# Microcontroller.net
KiCad netlist of a schematic drawn in Altium Designer
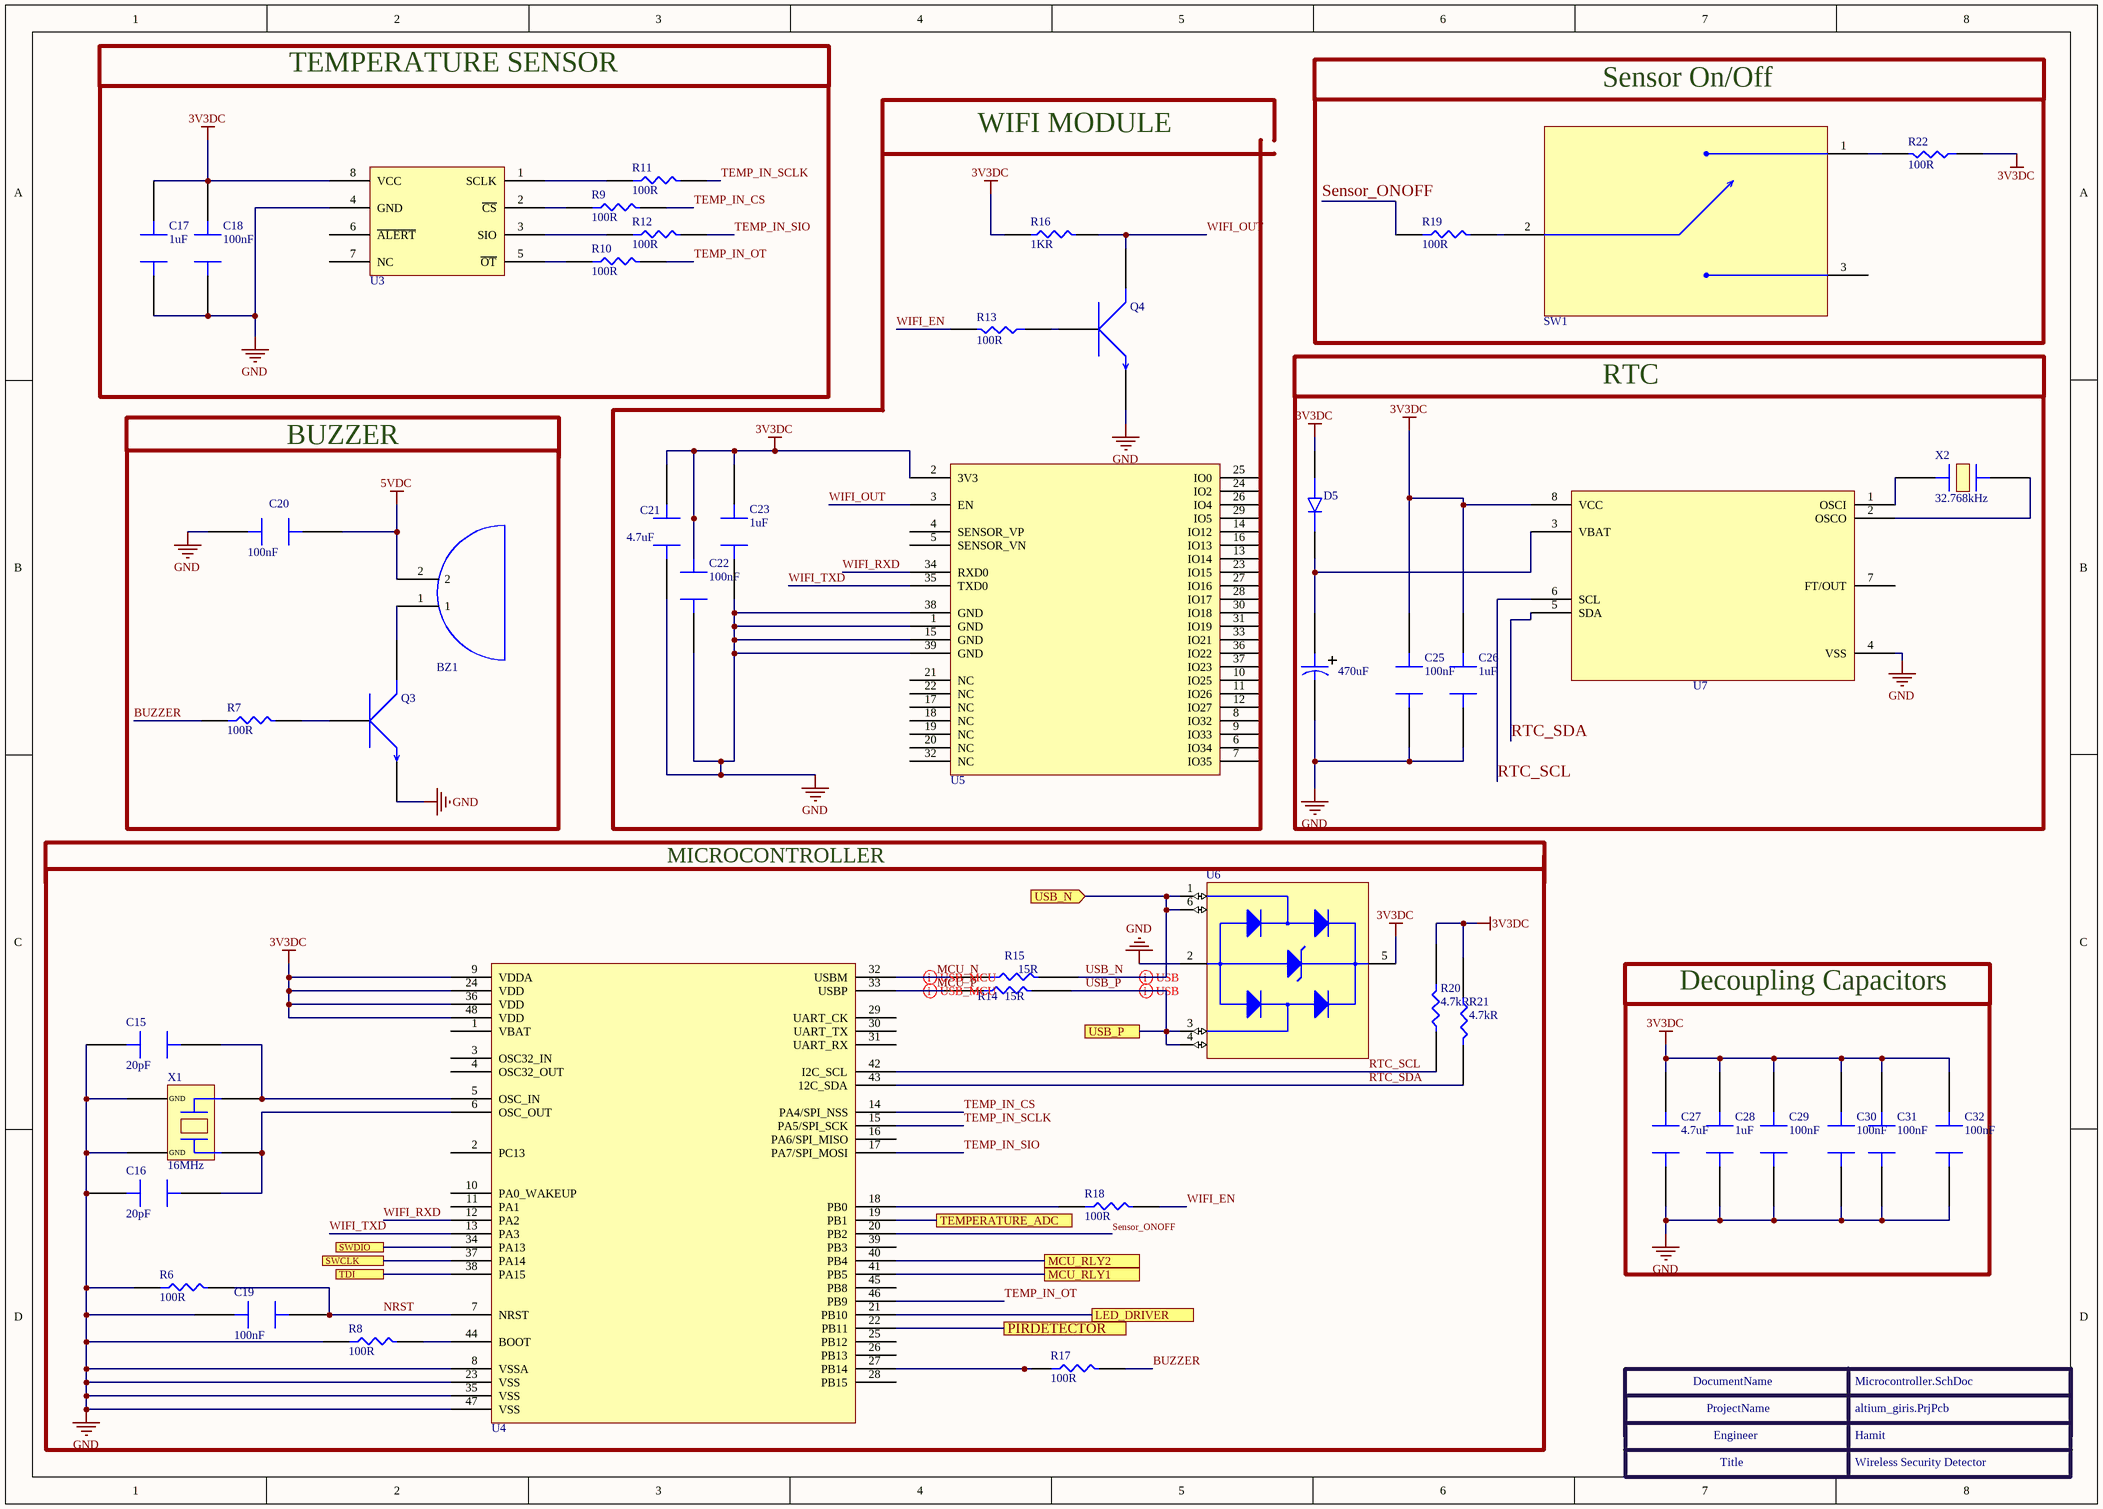
[diagram p0: Microcontroller.SchDoc]

(export (version "E")
  (design (tool "Eeschema 10.0.6"))
  (components
    (comp (ref "BZ1")
      (value "CMI-9605IC-0580T")
      (footprint "CMI-9605IC-0580T")
      (description "Buzzers Indicator, Internally Driven Magnetic 30mA 2.7kHz 80dB @ 5V, 10cm Through Hole PC Pins")
      (fields (field (name "MANUFACTURER") "CUI Devices") (field (name "DESIGNED BY") "Hamit"))
      (libsource (lib "giris_intlib") (part "CMI-9605IC-0580T"))
    )
    (comp (ref "C15")
      (value "CL10C200JB8NNNC")
      (footprint "CAP_0603")
      (fields
        (field (name "MANUFACTURER") "Samsung")
        (field (name "TOLERANCE") "5%")
        (field (name "VOLTAGE") "50V")
        (field (name "CAPACITANCE") "20pF")
        (field (name "DESIGNED BY") "Hamit")
      )
      (libsource (lib "giris_intlib") (part "CAP CER 20PF"))
    )
    (comp (ref "C16")
      (value "CL10C200JB8NNNC")
      (footprint "CAP_0603")
      (fields
        (field (name "MANUFACTURER") "Samsung")
        (field (name "TOLERANCE") "5%")
        (field (name "VOLTAGE") "50V")
        (field (name "CAPACITANCE") "20pF")
        (field (name "DESIGNED BY") "Hamit")
      )
      (libsource (lib "giris_intlib") (part "CAP CER 20PF"))
    )
    (comp (ref "C17")
      (value "CAP CER 1uF 0805")
      (footprint "cap_0805")
      (description "0805 0.1 uF ±10 % Tolerance 50 V X7R Multilayer Ceramic Capacitors")
      (fields
        (field (name "MANUFACTURER") "Samsung")
        (field (name "MANUFACTURER PART NUMBER") "CL21B104KBFNNNE")
        (field (name "CAPACITANCE") "1uF")
        (field (name "DESIGNED BY") "Hamit")
      )
      (libsource (lib "giris_intlib") (part "CAP CER 1uF 0805"))
    )
    (comp (ref "C18")
      (value "CL21B104KBCNNNC")
      (footprint "cap_0805")
      (fields
        (field (name "MANUFACTURER") "Samsung")
        (field (name "TOLERANCE") "10%")
        (field (name "VOLTAGE") "50V")
        (field (name "CAPACITANCE") "100nF")
        (field (name "DESIGNED BY") "Hamit")
      )
      (libsource (lib "giris_intlib") (part "CAP cer 100nF 0805"))
    )
    (comp (ref "C19")
      (value "CAP CER 100nF 0603")
      (footprint "CAP_0603")
      (fields
        (field (name "MANUFACTURER") "KEMET")
        (field (name "MANUFACTURER PART NUMBER") "C0603C104K5RACTU")
        (field (name "TOLERANCE") "10%")
        (field (name "CAPACITANCE") "100nF")
        (field (name "DESIGNED BY") "Hamit")
      )
      (libsource (lib "giris_intlib") (part "CAP CER 100nF 0603"))
    )
    (comp (ref "C20")
      (value "CAP CER 100nF 0603")
      (footprint "CAP_0603")
      (fields
        (field (name "MANUFACTURER") "KEMET")
        (field (name "MANUFACTURER PART NUMBER") "C0603C104K5RACTU")
        (field (name "TOLERANCE") "10%")
        (field (name "CAPACITANCE") "100nF")
        (field (name "DESIGNED BY") "Hamit")
      )
      (libsource (lib "giris_intlib") (part "CAP CER 100nF 0603"))
    )
    (comp (ref "C21")
      (value "CL21A475KAQNNNE")
      (footprint "cap_0805")
      (fields
        (field (name "MANUFACTURER") "Samsung")
        (field (name "TOLERANCE") "10%")
        (field (name "CAPACITANCE") "4.7uF")
        (field (name "DESIGNED BY") "Hamit")
      )
      (libsource (lib "giris_intlib") (part "cap_0805_4.7uF"))
    )
    (comp (ref "C22")
      (value "CL21B104KBCNNNC")
      (footprint "cap_0805")
      (fields
        (field (name "MANUFACTURER") "Samsung")
        (field (name "TOLERANCE") "10%")
        (field (name "VOLTAGE") "50V")
        (field (name "CAPACITANCE") "100nF")
        (field (name "DESIGNED BY") "Hamit")
      )
      (libsource (lib "giris_intlib") (part "CAP cer 100nF 0805"))
    )
    (comp (ref "C23")
      (value "CAP CER 1uF 0805")
      (footprint "cap_0805")
      (description "0805 0.1 uF ±10 % Tolerance 50 V X7R Multilayer Ceramic Capacitors")
      (fields
        (field (name "MANUFACTURER") "Samsung")
        (field (name "MANUFACTURER PART NUMBER") "CL21B104KBFNNNE")
        (field (name "CAPACITANCE") "1uF")
        (field (name "DESIGNED BY") "Hamit")
      )
      (libsource (lib "giris_intlib") (part "CAP CER 1uF 0805"))
    )
    (comp (ref "C24")
      (value "ESH477M050AH4AA")
      (footprint "cap_ESH477M050AH4AA")
      (description "Cap, 470UF, 50V, Alu Elec, Radial")
      (fields
        (field (name "MANUFACTURER") "KEMET")
        (field (name "TOLERANCE") "20%")
        (field (name "CAPACITANCE") "470uF")
        (field (name "DESIGNED BY") "Hamit")
      )
      (libsource (lib "giris_intlib") (part "CAP ALU 470uF"))
    )
    (comp (ref "C25")
      (value "CAP CER 100nF 0603")
      (footprint "CAP_0603")
      (fields
        (field (name "MANUFACTURER") "KEMET")
        (field (name "MANUFACTURER PART NUMBER") "C0603C104K5RACTU")
        (field (name "TOLERANCE") "10%")
        (field (name "CAPACITANCE") "100nF")
        (field (name "DESIGNED BY") "Hamit")
      )
      (libsource (lib "giris_intlib") (part "CAP CER 100nF 0603"))
    )
    (comp (ref "C26")
      (value "CAP CER 1uF 0805")
      (footprint "cap_0805")
      (description "0805 0.1 uF ±10 % Tolerance 50 V X7R Multilayer Ceramic Capacitors")
      (fields
        (field (name "MANUFACTURER") "Samsung")
        (field (name "MANUFACTURER PART NUMBER") "CL21B104KBFNNNE")
        (field (name "CAPACITANCE") "1uF")
        (field (name "DESIGNED BY") "Hamit")
      )
      (libsource (lib "giris_intlib") (part "CAP CER 1uF 0805"))
    )
    (comp (ref "C27")
      (value "CL21A475KAQNNNE")
      (footprint "cap_0805")
      (fields
        (field (name "MANUFACTURER") "Samsung")
        (field (name "TOLERANCE") "10%")
        (field (name "CAPACITANCE") "4.7uF")
        (field (name "DESIGNED BY") "Hamit")
      )
      (libsource (lib "giris_intlib") (part "CAP CER 4.7 uF"))
    )
    (comp (ref "C28")
      (value "CAP CER 1uF 0805")
      (footprint "cap_0805")
      (description "0805 0.1 uF ±10 % Tolerance 50 V X7R Multilayer Ceramic Capacitors")
      (fields
        (field (name "MANUFACTURER") "Samsung")
        (field (name "MANUFACTURER PART NUMBER") "CL21B104KBFNNNE")
        (field (name "CAPACITANCE") "1uF")
        (field (name "DESIGNED BY") "Hamit")
      )
      (libsource (lib "giris_intlib") (part "CAP CER 1uF 0805"))
    )
    (comp (ref "C29")
      (value "CAP CER 100nF 0603")
      (footprint "CAP_0603")
      (fields
        (field (name "MANUFACTURER") "KEMET")
        (field (name "MANUFACTURER PART NUMBER") "C0603C104K5RACTU")
        (field (name "TOLERANCE") "10%")
        (field (name "CAPACITANCE") "100nF")
        (field (name "DESIGNED BY") "Hamit")
      )
      (libsource (lib "giris_intlib") (part "CAP CER 100nF 0603"))
    )
    (comp (ref "C30")
      (value "CAP CER 100nF 0603")
      (footprint "CAP_0603")
      (fields
        (field (name "MANUFACTURER") "KEMET")
        (field (name "MANUFACTURER PART NUMBER") "C0603C104K5RACTU")
        (field (name "TOLERANCE") "10%")
        (field (name "CAPACITANCE") "100nF")
        (field (name "DESIGNED BY") "Hamit")
      )
      (libsource (lib "giris_intlib") (part "CAP CER 100nF 0603"))
    )
    (comp (ref "C31")
      (value "CAP CER 100nF 0603")
      (footprint "CAP_0603")
      (fields
        (field (name "MANUFACTURER") "KEMET")
        (field (name "MANUFACTURER PART NUMBER") "C0603C104K5RACTU")
        (field (name "TOLERANCE") "10%")
        (field (name "CAPACITANCE") "100nF")
        (field (name "DESIGNED BY") "Hamit")
      )
      (libsource (lib "giris_intlib") (part "CAP CER 100nF 0603"))
    )
    (comp (ref "C32")
      (value "CAP CER 100nF 0603")
      (footprint "CAP_0603")
      (fields
        (field (name "MANUFACTURER") "KEMET")
        (field (name "MANUFACTURER PART NUMBER") "C0603C104K5RACTU")
        (field (name "TOLERANCE") "10%")
        (field (name "CAPACITANCE") "100nF")
        (field (name "DESIGNED BY") "Hamit")
      )
      (libsource (lib "giris_intlib") (part "CAP CER 100nF 0603"))
    )
    (comp (ref "D5")
      (value "DIODE GEN PURP 75V 150MA SOD323F")
      (footprint "1N4148WS")
      (description "ON SEMICONDUCTOR - 1N4148WS - Small Signal Diode, Single, 75 V, 150 mA, 1 V, 4 ns")
      (fields
        (field (name "MANUFACTURER") "ON Semiconductor / Fairchild")
        (field (name "MANUFACTURER PART NUMBER") "1N4148WS")
        (field (name "DESIGNED BY") "Hamit")
      )
      (libsource (lib "giris_intlib") (part "1N4148WS"))
    )
    (comp (ref "Q3")
      (value "MMBT3904-7-F")
      (footprint "SSM3K357R,LF")
      (description "Transistor General Purpose BJT NPN 40 Volt 0.2A Automotive 3-Pin SOT-23")
      (fields (field (name "MANUFACTURER") "Diodes Zetex") (field (name "DESIGNED BY") "Hamit"))
      (libsource (lib "giris_intlib") (part "MMBT3904-7-F"))
    )
    (comp (ref "Q4")
      (value "MMBT3904-7-F")
      (footprint "SSM3K357R,LF")
      (description "Transistor General Purpose BJT NPN 40 Volt 0.2A Automotive 3-Pin SOT-23")
      (fields (field (name "MANUFACTURER") "Diodes Zetex") (field (name "DESIGNED BY") "Hamit"))
      (libsource (lib "giris_intlib") (part "MMBT3904-7-F"))
    )
    (comp (ref "R6")
      (value "RC0603FR-7W100RL")
      (footprint "RES_0603")
      (description "RESISTOR, 0603, 100R, 1%")
      (fields
        (field (name "MANUFACTURER") "Yageo")
        (field (name "TOLERANCE") "1%")
        (field (name "RESISTANCE") "100R")
      )
      (libsource (lib "giris_intlib") (part "RES 100 OHm"))
    )
    (comp (ref "R7")
      (value "RC0603FR-7W100RL")
      (footprint "RES_0603")
      (description "RESISTOR, 0603, 100R, 1%")
      (fields
        (field (name "MANUFACTURER") "Yageo")
        (field (name "TOLERANCE") "1%")
        (field (name "RESISTANCE") "100R")
      )
      (libsource (lib "giris_intlib") (part "RES 100 OHM"))
    )
    (comp (ref "R8")
      (value "RC0603FR-7W100RL")
      (footprint "RES_0603")
      (description "RESISTOR, 0603, 100R, 1%")
      (fields
        (field (name "MANUFACTURER") "Yageo")
        (field (name "TOLERANCE") "1%")
        (field (name "RESISTANCE") "100R")
      )
      (libsource (lib "giris_intlib") (part "RES 100 OHm"))
    )
    (comp (ref "R9")
      (value "RC0603FR-7W100RL")
      (footprint "RES_0603")
      (description "RESISTOR, 0603, 100R, 1%")
      (fields
        (field (name "MANUFACTURER") "Yageo")
        (field (name "TOLERANCE") "1%")
        (field (name "RESISTANCE") "100R")
      )
      (libsource (lib "giris_intlib") (part "RES 100 OHM"))
    )
    (comp (ref "R10")
      (value "RC0603FR-7W100RL")
      (footprint "RES_0603")
      (description "RESISTOR, 0603, 100R, 1%")
      (fields
        (field (name "MANUFACTURER") "Yageo")
        (field (name "TOLERANCE") "1%")
        (field (name "RESISTANCE") "100R")
      )
      (libsource (lib "giris_intlib") (part "RES 100 OHM"))
    )
    (comp (ref "R11")
      (value "RC0603FR-7W100RL")
      (footprint "RES_0603")
      (description "RESISTOR, 0603, 100R, 1%")
      (fields
        (field (name "MANUFACTURER") "Yageo")
        (field (name "TOLERANCE") "1%")
        (field (name "RESISTANCE") "100R")
      )
      (libsource (lib "giris_intlib") (part "RES 100 OHM"))
    )
    (comp (ref "R12")
      (value "RC0603FR-7W100RL")
      (footprint "RES_0603")
      (description "RESISTOR, 0603, 100R, 1%")
      (fields
        (field (name "MANUFACTURER") "Yageo")
        (field (name "TOLERANCE") "1%")
        (field (name "RESISTANCE") "100R")
      )
      (libsource (lib "giris_intlib") (part "RES 100 OHM"))
    )
    (comp (ref "R13")
      (value "RC0603FR-7W100RL")
      (footprint "RES_0603")
      (description "RESISTOR, 0603, 100R, 1%")
      (fields
        (field (name "MANUFACTURER") "Yageo")
        (field (name "TOLERANCE") "1%")
        (field (name "RESISTANCE") "100R")
      )
      (libsource (lib "giris_intlib") (part "RES 100 OHm"))
    )
    (comp (ref "R14")
      (value "rc0603jr-0715rl")
      (footprint "RES_0603")
      (fields
        (field (name "MANUFACTURER") "Yageo")
        (field (name "MANUFACTURER PART NUMBER") "RC0603JR-0715RL")
        (field (name "TOLERANCE") "5%")
        (field (name "RESISTANCE") "15R")
        (field (name "DESIGNED BY") "Hamit")
      )
      (libsource (lib "giris_intlib") (part "RES 15 OHM 0603"))
    )
    (comp (ref "R15")
      (value "rc0603jr-0715rl")
      (footprint "RES_0603")
      (fields
        (field (name "MANUFACTURER") "Yageo")
        (field (name "MANUFACTURER PART NUMBER") "RC0603JR-0715RL")
        (field (name "TOLERANCE") "5%")
        (field (name "RESISTANCE") "15R")
        (field (name "DESIGNED BY") "Hamit")
      )
      (libsource (lib "giris_intlib") (part "RES 15 OHM 0603"))
    )
    (comp (ref "R16")
      (value "RC0603FR-0710KL")
      (footprint "RES_0603")
      (description "RES 1K %1 OHM 0603 SMD")
      (fields
        (field (name "MANUFACTURER") "Yageo")
        (field (name "MANUFACTURER PART NUMBER") "RC0603JR-071KL")
        (field (name "RESISTANCE") "1KR")
        (field (name "DESIGNED BY") "Hamit")
      )
      (libsource (lib "giris_intlib") (part "RES 1K OHM 0603"))
    )
    (comp (ref "R17")
      (value "RC0603FR-7W100RL")
      (footprint "RES_0603")
      (description "RESISTOR, 0603, 100R, 1%")
      (fields
        (field (name "MANUFACTURER") "Yageo")
        (field (name "TOLERANCE") "1%")
        (field (name "RESISTANCE") "100R")
      )
      (libsource (lib "giris_intlib") (part "RES 100 OHM"))
    )
    (comp (ref "R18")
      (value "RC0603FR-7W100RL")
      (footprint "RES_0603")
      (description "RESISTOR, 0603, 100R, 1%")
      (fields
        (field (name "MANUFACTURER") "Yageo")
        (field (name "TOLERANCE") "1%")
        (field (name "RESISTANCE") "100R")
      )
      (libsource (lib "giris_intlib") (part "RES 100 OHM"))
    )
    (comp (ref "R19")
      (value "RC0603FR-7W100RL")
      (footprint "RES_0603")
      (description "RESISTOR, 0603, 100R, 1%")
      (fields
        (field (name "MANUFACTURER") "Yageo")
        (field (name "TOLERANCE") "1%")
        (field (name "RESISTANCE") "100R")
      )
      (libsource (lib "giris_intlib") (part "RES 100 OHM"))
    )
    (comp (ref "R20")
      (value "RC0603JR-074K7L")
      (footprint "RES_0603")
      (description "Res Thick Film 0603 4.7K Ohm 5% 0.1W(1/10W) ±100ppm/C Molded SMD Paper T/R")
      (fields
        (field (name "MANUFACTURER") "Yageo")
        (field (name "TOLERANCE") "5%")
        (field (name "RESISTANCE") "4.7kR")
        (field (name "DESIGNED BY") "Hamit")
      )
      (libsource (lib "giris_intlib") (part "RES 4K7 OHM"))
    )
    (comp (ref "R21")
      (value "RC0603JR-074K7L")
      (footprint "RES_0603")
      (description "Res Thick Film 0603 4.7K Ohm 5% 0.1W(1/10W) ±100ppm/C Molded SMD Paper T/R")
      (fields
        (field (name "MANUFACTURER") "Yageo")
        (field (name "TOLERANCE") "5%")
        (field (name "RESISTANCE") "4.7kR")
        (field (name "DESIGNED BY") "Hamit")
      )
      (libsource (lib "giris_intlib") (part "RES 4K7 OHM"))
    )
    (comp (ref "R22")
      (value "RC0603FR-7W100RL")
      (footprint "RES_0603")
      (description "RESISTOR, 0603, 100R, 1%")
      (fields
        (field (name "MANUFACTURER") "Yageo")
        (field (name "TOLERANCE") "1%")
        (field (name "RESISTANCE") "100R")
      )
      (libsource (lib "giris_intlib") (part "RES 100 OHM"))
    )
    (comp (ref "SW1")
      (value "EG1215AA")
      (footprint "EG1215AA")
      (description "Slide Switch, SPDT, 0.025A, 24V, SMD")
      (fields
        (field (name "MANUFACTURER") "E-Switch")
        (field (name "TOLERANCE") "4.95%")
        (field (name "DESIGNED BY") "Hamit")
      )
      (libsource (lib "giris_intlib") (part "EG1215AA"))
    )
    (comp (ref "U3")
      (value "MAX6662MSA+-ND")
      (footprint "LM2675MX-12/NOPB")
      (description "Temp Sensor Digital Serial (3-Wire, SPI) 8-Pin SOIC N Tube")
      (fields
        (field (name "MANUFACTURER") "Maxim")
        (field (name "MANUFACTURER PART NUMBER") "MAX6662MSA+")
        (field (name "DESIGNED BY") "Hamit")
      )
      (libsource (lib "giris_intlib") (part "MAX6662MSA+-ND"))
    )
    (comp (ref "U4")
      (value "STM32F103C6T7A")
      (footprint "LQFP-48")
      (description "IC MCU 32BIT 32KB FLASH 48LQFP")
      (fields (field (name "MANUFACTURER") "STMicroelectronics") (field (name "DESIGNED BY") "Hamit"))
      (libsource (lib "giris_intlib") (part "STM32F103C6T7A"))
    )
    (comp (ref "U5")
      (value "ESP32-WROOM-32E(4MB)")
      (footprint "ESP32-32")
      (fields (field (name "MANUFACTURER") "Espressif Systems") (field (name "DESIGNED BY") "Hamit"))
      (libsource (lib "giris_intlib") (part "ESP32-WROOM-32E(4MB)"))
    )
    (comp (ref "U6")
      (value "USBLC6-2SC6")
      (footprint "SOT23-6")
      (description "TVS DIODE 5.25V 17V SOT23-6")
      (fields (field (name "MANUFACTURER") "STMicroelectronics") (field (name "DESIGNED BY") "Hamit"))
      (libsource (lib "giris_intlib") (part "USB PROTECTION"))
    )
    (comp (ref "U7")
      (value "M41T00M6F")
      (footprint "LM2675MX-12/NOPB")
      (description "IC RTC CLK/CALENDAR I2C 8-SOIC")
      (fields (field (name "MANUFACTURER") "STMicroelectronics") (field (name "DESIGNED BY") "Hamit"))
      (libsource (lib "giris_intlib") (part "M41T00M6F"))
    )
    (comp (ref "X1")
      (value "ECS-160-20-30B-TR")
      (footprint "CRYSTAL_ECS-160-20-30B-TR")
      (description "CRYSTAL 16.0000MHZ 20PF SMD")
      (fields
        (field (name "MANUFACTURER") "ECS International")
        (field (name "TOLERANCE") "50ppm")
        (field (name "FREQUENCY") "16MHz")
        (field (name "DESIGNED BY") "Hamit")
      )
      (libsource (lib "giris_intlib") (part "CRYSTAL 16MHZ 20PF SMD"))
    )
    (comp (ref "X2")
      (value "ABS05-32.768KHZ-T")
      (footprint "ABS05_crystal")
      (description "ABRACON - ABS05-32.768KHZ-T - Crystal, 32.768 kHz, SMD, 1.6mm x 1mm, 12.5 pF, 20 ppm, ABS05 Series")
      (fields
        (field (name "MANUFACTURER") "Abracon")
        (field (name "TOLERANCE") "20ppm")
        (field (name "FREQUENCY") "32.768kHz")
        (field (name "DESIGNED BY") "Hamit")
      )
      (libsource (lib "giris_intlib") (part "CRYSTAL 32768kHz"))
    )
  )
  (nets
    (net (code "1") (name "/BUZZER") (class "Default")
      (node (ref "R17") (pin "2") (pinfunction "2_2") (pintype "passive"))
      (node (ref "R7") (pin "1") (pinfunction "1_1") (pintype "passive"))
    )
    (net (code "2") (name "/LED_DRIVER") (class "Default")
      (node (ref "U4") (pin "21") (pinfunction "PB10_21") (pintype "passive"))
    )
    (net (code "3") (name "/MCU_N") (class "Default")
      (node (ref "R15") (pin "1") (pinfunction "1_1") (pintype "passive"))
      (node (ref "U4") (pin "32") (pinfunction "USBM_32") (pintype "passive"))
    )
    (net (code "4") (name "/MCU_P") (class "Default")
      (node (ref "R14") (pin "1") (pinfunction "1_1") (pintype "passive"))
      (node (ref "U4") (pin "33") (pinfunction "USBP_33") (pintype "passive"))
    )
    (net (code "5") (name "/MCU_RLY1") (class "Default")
      (node (ref "U4") (pin "41") (pinfunction "PB5_41") (pintype "passive"))
    )
    (net (code "6") (name "/MCU_RLY2") (class "Default")
      (node (ref "U4") (pin "40") (pinfunction "PB4_40") (pintype "passive"))
    )
    (net (code "7") (name "/NRST") (class "Default")
      (node (ref "C19") (pin "1") (pinfunction "1_1") (pintype "passive"))
      (node (ref "R6") (pin "2") (pinfunction "2_2") (pintype "passive"))
      (node (ref "U4") (pin "7") (pinfunction "NRST_7") (pintype "passive"))
    )
    (net (code "8") (name "/PIRDETECTOR") (class "Default")
      (node (ref "U4") (pin "22") (pinfunction "PB11_22") (pintype "passive"))
    )
    (net (code "9") (name "/RTC_SCL") (class "Default")
      (node (ref "R20") (pin "1") (pinfunction "1_1") (pintype "passive"))
      (node (ref "U4") (pin "42") (pinfunction "I2C_SCL_42") (pintype "passive"))
      (node (ref "U7") (pin "6") (pinfunction "SCL_6") (pintype "passive"))
    )
    (net (code "10") (name "/RTC_SDA") (class "Default")
      (node (ref "R21") (pin "2") (pinfunction "2_2") (pintype "passive"))
      (node (ref "U4") (pin "43") (pinfunction "12C_SDA_43") (pintype "passive"))
      (node (ref "U7") (pin "5") (pinfunction "SDA_5") (pintype "passive"))
    )
    (net (code "11") (name "/SWCLK") (class "Default")
      (node (ref "U4") (pin "37") (pinfunction "PA14_37") (pintype "passive"))
    )
    (net (code "12") (name "/SWDIO") (class "Default")
      (node (ref "U4") (pin "34") (pinfunction "PA13_34") (pintype "passive"))
    )
    (net (code "13") (name "/Sensor_ONOFF") (class "Default")
      (node (ref "R19") (pin "1") (pinfunction "1_1") (pintype "passive"))
      (node (ref "U4") (pin "20") (pinfunction "PB2_20") (pintype "passive"))
    )
    (net (code "14") (name "/TDI") (class "Default")
      (node (ref "U4") (pin "38") (pinfunction "PA15_38") (pintype "passive"))
    )
    (net (code "15") (name "/TEMPERATURE_ADC") (class "Default")
      (node (ref "U4") (pin "19") (pinfunction "PB1_19") (pintype "passive"))
    )
    (net (code "16") (name "/TEMP_IN_CS") (class "Default")
      (node (ref "R9") (pin "2") (pinfunction "2_2") (pintype "passive"))
      (node (ref "U4") (pin "14") (pinfunction "PA4/SPI_NSS_14") (pintype "passive"))
    )
    (net (code "17") (name "/TEMP_IN_OT") (class "Default")
      (node (ref "R10") (pin "2") (pinfunction "2_2") (pintype "passive"))
      (node (ref "U4") (pin "46") (pinfunction "PB9_46") (pintype "passive"))
    )
    (net (code "18") (name "/TEMP_IN_SCLK") (class "Default")
      (node (ref "R11") (pin "2") (pinfunction "2_2") (pintype "passive"))
      (node (ref "U4") (pin "15") (pinfunction "PA5/SPI_SCK_15") (pintype "passive"))
    )
    (net (code "19") (name "/TEMP_IN_SIO") (class "Default")
      (node (ref "R12") (pin "2") (pinfunction "2_2") (pintype "passive"))
      (node (ref "U4") (pin "17") (pinfunction "PA7/SPI_MOSI_17") (pintype "passive"))
    )
    (net (code "20") (name "/USB_N") (class "Default")
      (node (ref "R15") (pin "2") (pinfunction "2_2") (pintype "passive"))
      (node (ref "U6") (pin "1") (pinfunction "I/O1_1") (pintype "bidirectional"))
      (node (ref "U6") (pin "6") (pinfunction "I/O1_6") (pintype "bidirectional"))
    )
    (net (code "21") (name "/USB_P") (class "Default")
      (node (ref "R14") (pin "2") (pinfunction "2_2") (pintype "passive"))
      (node (ref "U6") (pin "3") (pinfunction "I/O2_3") (pintype "bidirectional"))
      (node (ref "U6") (pin "4") (pinfunction "I/O2_4") (pintype "bidirectional"))
    )
    (net (code "22") (name "/WIFI_EN") (class "Default")
      (node (ref "R13") (pin "2") (pinfunction "2_2") (pintype "passive"))
      (node (ref "R18") (pin "2") (pinfunction "2_2") (pintype "passive"))
    )
    (net (code "23") (name "/WIFI_OUT") (class "Default")
      (node (ref "Q4") (pin "3") (pinfunction "C_3") (pintype "passive"))
      (node (ref "R16") (pin "1") (pinfunction "1_1") (pintype "passive"))
      (node (ref "U5") (pin "3") (pinfunction "EN_3") (pintype "passive"))
    )
    (net (code "24") (name "/WIFI_RXD") (class "Default")
      (node (ref "U4") (pin "12") (pinfunction "PA2_12") (pintype "passive"))
      (node (ref "U5") (pin "34") (pinfunction "RXD0_34") (pintype "passive"))
    )
    (net (code "25") (name "/WIFI_TXD") (class "Default")
      (node (ref "U4") (pin "13") (pinfunction "PA3_13") (pintype "passive"))
      (node (ref "U5") (pin "35") (pinfunction "TXD0_35") (pintype "passive"))
    )
    (net (code "26") (name "3V3DC") (class "Default")
      (node (ref "C17") (pin "2") (pinfunction "2_2") (pintype "passive"))
      (node (ref "C18") (pin "2") (pinfunction "2_2") (pintype "passive"))
      (node (ref "C21") (pin "2") (pinfunction "2_2") (pintype "passive"))
      (node (ref "C22") (pin "2") (pinfunction "2_2") (pintype "passive"))
      (node (ref "C23") (pin "2") (pinfunction "2_2") (pintype "passive"))
      (node (ref "C25") (pin "2") (pinfunction "2_2") (pintype "passive"))
      (node (ref "C26") (pin "2") (pinfunction "2_2") (pintype "passive"))
      (node (ref "C27") (pin "2") (pinfunction "2_2") (pintype "passive"))
      (node (ref "C28") (pin "2") (pinfunction "2_2") (pintype "passive"))
      (node (ref "C29") (pin "2") (pinfunction "2_2") (pintype "passive"))
      (node (ref "C30") (pin "2") (pinfunction "2_2") (pintype "passive"))
      (node (ref "C31") (pin "2") (pinfunction "2_2") (pintype "passive"))
      (node (ref "C32") (pin "2") (pinfunction "2_2") (pintype "passive"))
      (node (ref "D5") (pin "A") (pinfunction "A_A") (pintype "passive"))
      (node (ref "R16") (pin "2") (pinfunction "2_2") (pintype "passive"))
      (node (ref "R20") (pin "2") (pinfunction "2_2") (pintype "passive"))
      (node (ref "R21") (pin "1") (pinfunction "1_1") (pintype "passive"))
      (node (ref "R22") (pin "1") (pinfunction "1_1") (pintype "passive"))
      (node (ref "U3") (pin "8") (pinfunction "VCC_8") (pintype "passive"))
      (node (ref "U4") (pin "24") (pinfunction "VDD_24") (pintype "passive"))
      (node (ref "U4") (pin "36") (pinfunction "VDD_36") (pintype "passive"))
      (node (ref "U4") (pin "48") (pinfunction "VDD_48") (pintype "passive"))
      (node (ref "U4") (pin "9") (pinfunction "VDDA_9") (pintype "passive"))
      (node (ref "U5") (pin "2") (pinfunction "3V3_2") (pintype "passive"))
      (node (ref "U6") (pin "5") (pinfunction "VBUS_5") (pintype "power_in"))
      (node (ref "U7") (pin "8") (pinfunction "VCC_8") (pintype "passive"))
    )
    (net (code "27") (name "5VDC") (class "Default")
      (node (ref "BZ1") (pin "2") (pinfunction "2_2") (pintype "passive"))
      (node (ref "C20") (pin "2") (pinfunction "2_2") (pintype "passive"))
    )
    (net (code "28") (name "GND") (class "Default")
      (node (ref "C15") (pin "2") (pinfunction "2_2") (pintype "passive"))
      (node (ref "C16") (pin "2") (pinfunction "2_2") (pintype "passive"))
      (node (ref "C17") (pin "1") (pinfunction "1_1") (pintype "passive"))
      (node (ref "C18") (pin "1") (pinfunction "1_1") (pintype "passive"))
      (node (ref "C19") (pin "2") (pinfunction "2_2") (pintype "passive"))
      (node (ref "C20") (pin "1") (pinfunction "1_1") (pintype "passive"))
      (node (ref "C21") (pin "1") (pinfunction "1_1") (pintype "passive"))
      (node (ref "C22") (pin "1") (pinfunction "1_1") (pintype "passive"))
      (node (ref "C23") (pin "1") (pinfunction "1_1") (pintype "passive"))
      (node (ref "C24") (pin "2") (pinfunction "2_2") (pintype "passive"))
      (node (ref "C25") (pin "1") (pinfunction "1_1") (pintype "passive"))
      (node (ref "C26") (pin "1") (pinfunction "1_1") (pintype "passive"))
      (node (ref "C27") (pin "1") (pinfunction "1_1") (pintype "passive"))
      (node (ref "C28") (pin "1") (pinfunction "1_1") (pintype "passive"))
      (node (ref "C29") (pin "1") (pinfunction "1_1") (pintype "passive"))
      (node (ref "C30") (pin "1") (pinfunction "1_1") (pintype "passive"))
      (node (ref "C31") (pin "1") (pinfunction "1_1") (pintype "passive"))
      (node (ref "C32") (pin "1") (pinfunction "1_1") (pintype "passive"))
      (node (ref "Q3") (pin "2") (pinfunction "E_2") (pintype "passive"))
      (node (ref "Q4") (pin "2") (pinfunction "E_2") (pintype "passive"))
      (node (ref "R6") (pin "1") (pinfunction "1_1") (pintype "passive"))
      (node (ref "R8") (pin "1") (pinfunction "1_1") (pintype "passive"))
      (node (ref "U3") (pin "4") (pinfunction "GND_4") (pintype "passive"))
      (node (ref "U4") (pin "23") (pinfunction "VSS_23") (pintype "passive"))
      (node (ref "U4") (pin "35") (pinfunction "VSS_35") (pintype "passive"))
      (node (ref "U4") (pin "47") (pinfunction "VSS_47") (pintype "passive"))
      (node (ref "U4") (pin "8") (pinfunction "VSSA_8") (pintype "passive"))
      (node (ref "U5") (pin "1") (pinfunction "GND_1") (pintype "passive"))
      (node (ref "U5") (pin "15") (pinfunction "GND_15") (pintype "passive"))
      (node (ref "U5") (pin "38") (pinfunction "GND_38") (pintype "passive"))
      (node (ref "U5") (pin "39") (pinfunction "GND_39") (pintype "passive"))
      (node (ref "U6") (pin "2") (pinfunction "GND_2") (pintype "power_in"))
      (node (ref "U7") (pin "4") (pinfunction "VSS_4") (pintype "passive"))
      (node (ref "X1") (pin "2") (pinfunction "GND_2") (pintype "passive"))
      (node (ref "X1") (pin "4") (pinfunction "GND_4") (pintype "passive"))
    )
    (net (code "29") (name "Net-(Q3-B)") (class "Default")
      (node (ref "Q3") (pin "1") (pinfunction "B_1") (pintype "passive"))
      (node (ref "R7") (pin "2") (pinfunction "2_2") (pintype "passive"))
    )
    (net (code "30") (name "Net-(Q3-C)") (class "Default")
      (node (ref "BZ1") (pin "1") (pinfunction "1_1") (pintype "passive"))
      (node (ref "Q3") (pin "3") (pinfunction "C_3") (pintype "passive"))
    )
    (net (code "31") (name "Net-(Q4-B)") (class "Default")
      (node (ref "Q4") (pin "1") (pinfunction "B_1") (pintype "passive"))
      (node (ref "R13") (pin "1") (pinfunction "1_1") (pintype "passive"))
    )
    (net (code "32") (name "Net-(R19-Pad2)") (class "Default")
      (node (ref "R19") (pin "2") (pinfunction "2_2") (pintype "passive"))
      (node (ref "SW1") (pin "2") (pinfunction "2_2") (pintype "passive"))
    )
    (net (code "33") (name "Net-(R22-Pad2)") (class "Default")
      (node (ref "R22") (pin "2") (pinfunction "2_2") (pintype "passive"))
      (node (ref "SW1") (pin "1") (pinfunction "1_1") (pintype "passive"))
    )
    (net (code "34") (name "Net-(U3-SCLK)") (class "Default")
      (node (ref "R11") (pin "1") (pinfunction "1_1") (pintype "passive"))
      (node (ref "U3") (pin "1") (pinfunction "SCLK_1") (pintype "passive"))
    )
    (net (code "35") (name "Net-(U3-SIO)") (class "Default")
      (node (ref "R12") (pin "1") (pinfunction "1_1") (pintype "passive"))
      (node (ref "U3") (pin "3") (pinfunction "SIO_3") (pintype "passive"))
    )
    (net (code "36") (name "Net-(U3-~{CS})") (class "Default")
      (node (ref "R9") (pin "1") (pinfunction "1_1") (pintype "passive"))
      (node (ref "U3") (pin "2") (pinfunction "~{CS}_2") (pintype "passive"))
    )
    (net (code "37") (name "Net-(U3-~{OT})") (class "Default")
      (node (ref "R10") (pin "1") (pinfunction "1_1") (pintype "passive"))
      (node (ref "U3") (pin "5") (pinfunction "~{OT}_5") (pintype "passive"))
    )
    (net (code "38") (name "Net-(U4-BOOT)") (class "Default")
      (node (ref "R8") (pin "2") (pinfunction "2_2") (pintype "passive"))
      (node (ref "U4") (pin "44") (pinfunction "BOOT_44") (pintype "passive"))
    )
    (net (code "39") (name "Net-(U4-OSC_IN)") (class "Default")
      (node (ref "C15") (pin "1") (pinfunction "1_1") (pintype "passive"))
      (node (ref "U4") (pin "5") (pinfunction "OSC_IN_5") (pintype "passive"))
      (node (ref "X1") (pin "3") (pinfunction "3_3") (pintype "passive"))
    )
    (net (code "40") (name "Net-(U4-OSC_OUT)") (class "Default")
      (node (ref "C16") (pin "1") (pinfunction "1_1") (pintype "passive"))
      (node (ref "U4") (pin "6") (pinfunction "OSC_OUT_6") (pintype "passive"))
      (node (ref "X1") (pin "1") (pinfunction "1_1") (pintype "passive"))
    )
    (net (code "41") (name "Net-(U4-PB0)") (class "Default")
      (node (ref "R18") (pin "1") (pinfunction "1_1") (pintype "passive"))
      (node (ref "U4") (pin "18") (pinfunction "PB0_18") (pintype "passive"))
    )
    (net (code "42") (name "Net-(U4-PB14)") (class "Default")
      (node (ref "R17") (pin "1") (pinfunction "1_1") (pintype "passive"))
      (node (ref "U4") (pin "27") (pinfunction "PB14_27") (pintype "passive"))
    )
    (net (code "43") (name "Net-(U7-OSCI)") (class "Default")
      (node (ref "U7") (pin "1") (pinfunction "OSCI_1") (pintype "passive"))
      (node (ref "X2") (pin "1") (pinfunction "1_1") (pintype "passive"))
    )
    (net (code "44") (name "Net-(U7-OSCO)") (class "Default")
      (node (ref "U7") (pin "2") (pinfunction "OSCO_2") (pintype "passive"))
      (node (ref "X2") (pin "2") (pinfunction "2_2") (pintype "passive"))
    )
    (net (code "45") (name "Net-(U7-VBAT)") (class "Default")
      (node (ref "C24") (pin "1") (pinfunction "1_1") (pintype "passive"))
      (node (ref "D5") (pin "C") (pinfunction "C_C") (pintype "passive"))
      (node (ref "U7") (pin "3") (pinfunction "VBAT_3") (pintype "passive"))
    )
    (net (code "46") (name "unconnected-(SW1-Pad3)") (class "Default")
      (node (ref "SW1") (pin "3") (pinfunction "3_3") (pintype "passive"))
    )
    (net (code "47") (name "unconnected-(U3-NC-Pad7)") (class "Default")
      (node (ref "U3") (pin "7") (pinfunction "NC_7") (pintype "passive"))
    )
    (net (code "48") (name "unconnected-(U3-~{ALERT}-Pad6)") (class "Default")
      (node (ref "U3") (pin "6") (pinfunction "~{ALERT}_6") (pintype "passive"))
    )
    (net (code "49") (name "unconnected-(U4-OSC32_IN-Pad3)") (class "Default")
      (node (ref "U4") (pin "3") (pinfunction "OSC32_IN_3") (pintype "passive"))
    )
    (net (code "50") (name "unconnected-(U4-OSC32_OUT-Pad4)") (class "Default")
      (node (ref "U4") (pin "4") (pinfunction "OSC32_OUT_4") (pintype "passive"))
    )
    (net (code "51") (name "unconnected-(U4-PA0_WAKEUP-Pad10)") (class "Default")
      (node (ref "U4") (pin "10") (pinfunction "PA0_WAKEUP_10") (pintype "passive"))
    )
    (net (code "52") (name "unconnected-(U4-PA1-Pad11)") (class "Default")
      (node (ref "U4") (pin "11") (pinfunction "PA1_11") (pintype "passive"))
    )
    (net (code "53") (name "unconnected-(U4-PA6{slash}SPI_MISO-Pad16)") (class "Default")
      (node (ref "U4") (pin "16") (pinfunction "PA6/SPI_MISO_16") (pintype "passive"))
    )
    (net (code "54") (name "unconnected-(U4-PB3-Pad39)") (class "Default")
      (node (ref "U4") (pin "39") (pinfunction "PB3_39") (pintype "passive"))
    )
    (net (code "55") (name "unconnected-(U4-PB8-Pad45)") (class "Default")
      (node (ref "U4") (pin "45") (pinfunction "PB8_45") (pintype "passive"))
    )
    (net (code "56") (name "unconnected-(U4-PB12-Pad25)") (class "Default")
      (node (ref "U4") (pin "25") (pinfunction "PB12_25") (pintype "passive"))
    )
    (net (code "57") (name "unconnected-(U4-PB13-Pad26)") (class "Default")
      (node (ref "U4") (pin "26") (pinfunction "PB13_26") (pintype "passive"))
    )
    (net (code "58") (name "unconnected-(U4-PB15-Pad28)") (class "Default")
      (node (ref "U4") (pin "28") (pinfunction "PB15_28") (pintype "passive"))
    )
    (net (code "59") (name "unconnected-(U4-PC13-Pad2)") (class "Default")
      (node (ref "U4") (pin "2") (pinfunction "PC13_2") (pintype "passive"))
    )
    (net (code "60") (name "unconnected-(U4-UART_CK-Pad29)") (class "Default")
      (node (ref "U4") (pin "29") (pinfunction "UART_CK_29") (pintype "passive"))
    )
    (net (code "61") (name "unconnected-(U4-UART_RX-Pad31)") (class "Default")
      (node (ref "U4") (pin "31") (pinfunction "UART_RX_31") (pintype "passive"))
    )
    (net (code "62") (name "unconnected-(U4-UART_TX-Pad30)") (class "Default")
      (node (ref "U4") (pin "30") (pinfunction "UART_TX_30") (pintype "passive"))
    )
    (net (code "63") (name "unconnected-(U4-VBAT-Pad1)") (class "Default")
      (node (ref "U4") (pin "1") (pinfunction "VBAT_1") (pintype "passive"))
    )
    (net (code "64") (name "unconnected-(U5-IO0-Pad25)") (class "Default")
      (node (ref "U5") (pin "25") (pinfunction "IO0_25") (pintype "passive"))
    )
    (net (code "65") (name "unconnected-(U5-IO2-Pad24)") (class "Default")
      (node (ref "U5") (pin "24") (pinfunction "IO2_24") (pintype "passive"))
    )
    (net (code "66") (name "unconnected-(U5-IO4-Pad26)") (class "Default")
      (node (ref "U5") (pin "26") (pinfunction "IO4_26") (pintype "passive"))
    )
    (net (code "67") (name "unconnected-(U5-IO5-Pad29)") (class "Default")
      (node (ref "U5") (pin "29") (pinfunction "IO5_29") (pintype "passive"))
    )
    (net (code "68") (name "unconnected-(U5-IO12-Pad14)") (class "Default")
      (node (ref "U5") (pin "14") (pinfunction "IO12_14") (pintype "passive"))
    )
    (net (code "69") (name "unconnected-(U5-IO13-Pad16)") (class "Default")
      (node (ref "U5") (pin "16") (pinfunction "IO13_16") (pintype "passive"))
    )
    (net (code "70") (name "unconnected-(U5-IO14-Pad13)") (class "Default")
      (node (ref "U5") (pin "13") (pinfunction "IO14_13") (pintype "passive"))
    )
    (net (code "71") (name "unconnected-(U5-IO15-Pad23)") (class "Default")
      (node (ref "U5") (pin "23") (pinfunction "IO15_23") (pintype "passive"))
    )
    (net (code "72") (name "unconnected-(U5-IO16-Pad27)") (class "Default")
      (node (ref "U5") (pin "27") (pinfunction "IO16_27") (pintype "passive"))
    )
    (net (code "73") (name "unconnected-(U5-IO17-Pad28)") (class "Default")
      (node (ref "U5") (pin "28") (pinfunction "IO17_28") (pintype "passive"))
    )
    (net (code "74") (name "unconnected-(U5-IO18-Pad30)") (class "Default")
      (node (ref "U5") (pin "30") (pinfunction "IO18_30") (pintype "passive"))
    )
    (net (code "75") (name "unconnected-(U5-IO19-Pad31)") (class "Default")
      (node (ref "U5") (pin "31") (pinfunction "IO19_31") (pintype "passive"))
    )
    (net (code "76") (name "unconnected-(U5-IO21-Pad33)") (class "Default")
      (node (ref "U5") (pin "33") (pinfunction "IO21_33") (pintype "passive"))
    )
    (net (code "77") (name "unconnected-(U5-IO22-Pad36)") (class "Default")
      (node (ref "U5") (pin "36") (pinfunction "IO22_36") (pintype "passive"))
    )
    (net (code "78") (name "unconnected-(U5-IO23-Pad37)") (class "Default")
      (node (ref "U5") (pin "37") (pinfunction "IO23_37") (pintype "passive"))
    )
    (net (code "79") (name "unconnected-(U5-IO25-Pad10)") (class "Default")
      (node (ref "U5") (pin "10") (pinfunction "IO25_10") (pintype "passive"))
    )
    (net (code "80") (name "unconnected-(U5-IO26-Pad11)") (class "Default")
      (node (ref "U5") (pin "11") (pinfunction "IO26_11") (pintype "passive"))
    )
    (net (code "81") (name "unconnected-(U5-IO27-Pad12)") (class "Default")
      (node (ref "U5") (pin "12") (pinfunction "IO27_12") (pintype "passive"))
    )
    (net (code "82") (name "unconnected-(U5-IO32-Pad8)") (class "Default")
      (node (ref "U5") (pin "8") (pinfunction "IO32_8") (pintype "passive"))
    )
    (net (code "83") (name "unconnected-(U5-IO33-Pad9)") (class "Default")
      (node (ref "U5") (pin "9") (pinfunction "IO33_9") (pintype "passive"))
    )
    (net (code "84") (name "unconnected-(U5-IO34-Pad6)") (class "Default")
      (node (ref "U5") (pin "6") (pinfunction "IO34_6") (pintype "passive"))
    )
    (net (code "85") (name "unconnected-(U5-IO35-Pad7)") (class "Default")
      (node (ref "U5") (pin "7") (pinfunction "IO35_7") (pintype "passive"))
    )
    (net (code "86") (name "unconnected-(U5-NC-Pad17)") (class "Default")
      (node (ref "U5") (pin "17") (pinfunction "NC_17") (pintype "passive"))
    )
    (net (code "87") (name "unconnected-(U5-NC-Pad18)") (class "Default")
      (node (ref "U5") (pin "18") (pinfunction "NC_18") (pintype "passive"))
    )
    (net (code "88") (name "unconnected-(U5-NC-Pad19)") (class "Default")
      (node (ref "U5") (pin "19") (pinfunction "NC_19") (pintype "passive"))
    )
    (net (code "89") (name "unconnected-(U5-NC-Pad20)") (class "Default")
      (node (ref "U5") (pin "20") (pinfunction "NC_20") (pintype "passive"))
    )
    (net (code "90") (name "unconnected-(U5-NC-Pad21)") (class "Default")
      (node (ref "U5") (pin "21") (pinfunction "NC_21") (pintype "passive"))
    )
    (net (code "91") (name "unconnected-(U5-NC-Pad22)") (class "Default")
      (node (ref "U5") (pin "22") (pinfunction "NC_22") (pintype "passive"))
    )
    (net (code "92") (name "unconnected-(U5-NC-Pad32)") (class "Default")
      (node (ref "U5") (pin "32") (pinfunction "NC_32") (pintype "passive"))
    )
    (net (code "93") (name "unconnected-(U5-SENSOR_VN-Pad5)") (class "Default")
      (node (ref "U5") (pin "5") (pinfunction "SENSOR_VN_5") (pintype "passive"))
    )
    (net (code "94") (name "unconnected-(U5-SENSOR_VP-Pad4)") (class "Default")
      (node (ref "U5") (pin "4") (pinfunction "SENSOR_VP_4") (pintype "passive"))
    )
    (net (code "95") (name "unconnected-(U7-FT{slash}OUT-Pad7)") (class "Default")
      (node (ref "U7") (pin "7") (pinfunction "FT/OUT_7") (pintype "passive"))
    )
  )
)
